# IntegratedSensor-nc8430win7.net
KiCad netlist of a schematic drawn in EAGLE
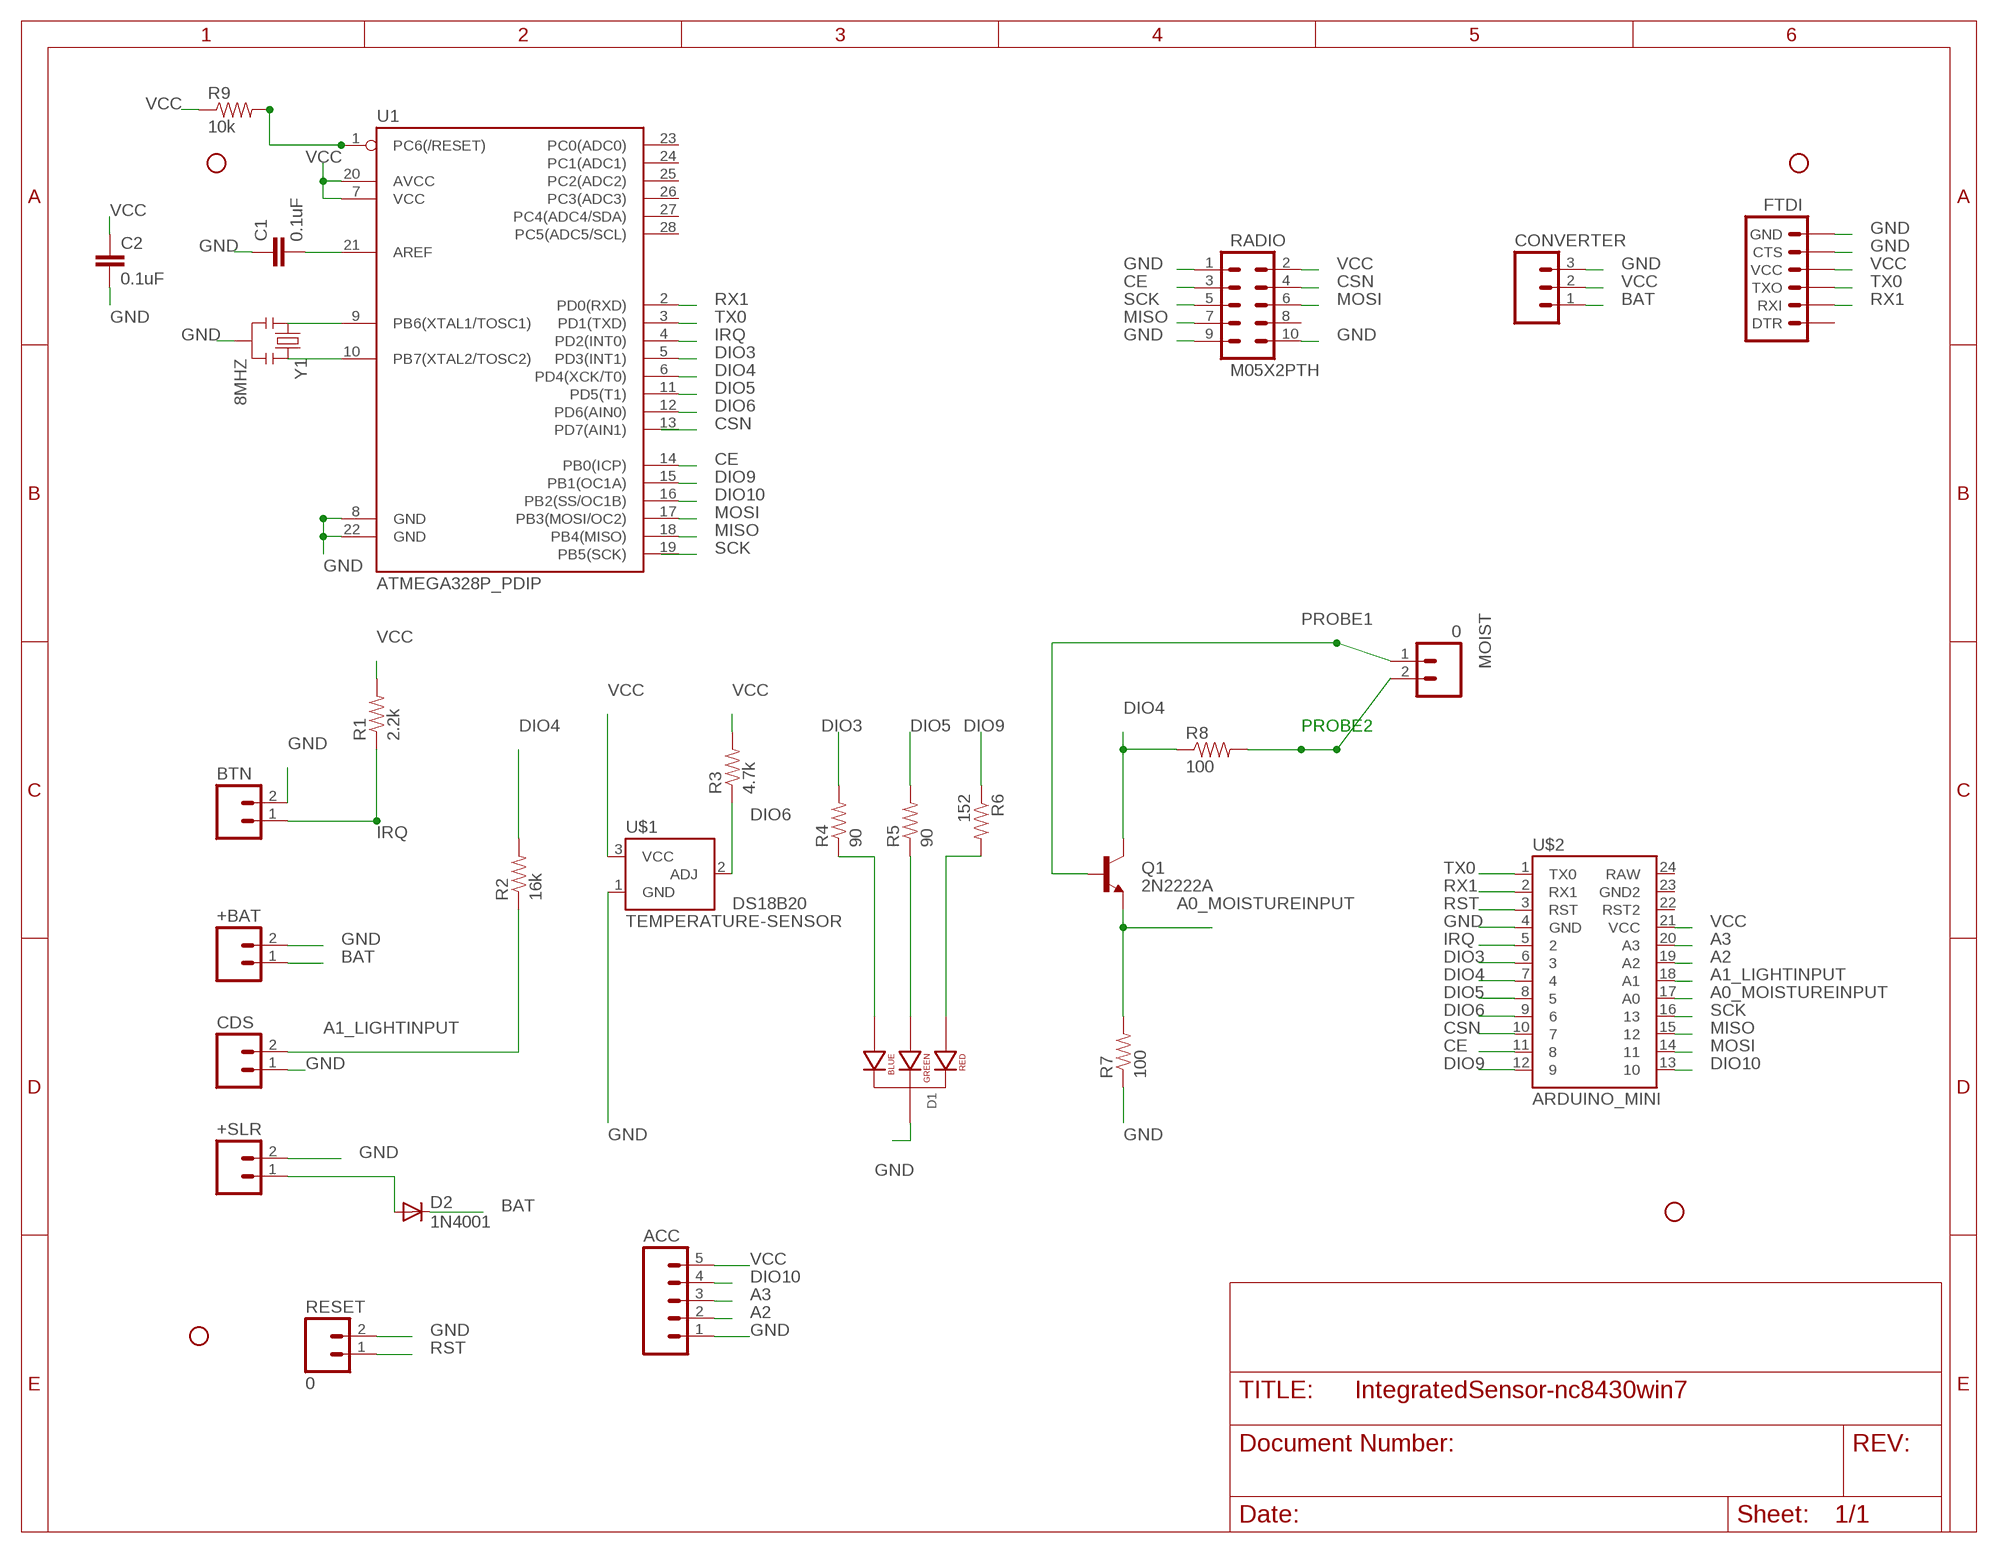
[diagram p0: schematic, sheet 1]

(export (version "E")
  (design (tool "Eeschema 10.0.6"))
  (components
    (comp (ref "+BAT")
      (value "M02PTH")
      (footprint "eagle-import:1X02")
      (libsource (lib "eagle-import") (part "M02PTH"))
    )
    (comp (ref "+SLR")
      (value "M02PTH")
      (footprint "eagle-import:1X02")
      (libsource (lib "eagle-import") (part "M02PTH"))
    )
    (comp (ref "ACC")
      (value "M05PTH")
      (footprint "eagle-import:1X05")
      (libsource (lib "eagle-import") (part "M05PTH"))
    )
    (comp (ref "BTN")
      (value "M02PTH")
      (footprint "eagle-import:1X02")
      (libsource (lib "eagle-import") (part "M02PTH"))
    )
    (comp (ref "C1")
      (value "0.1uF")
      (footprint "eagle-import:0402-CAP")
      (libsource (lib "eagle-import") (part "0.1UF-25V(+80/-20%)(0603)"))
    )
    (comp (ref "C2")
      (value "0.1uF")
      (footprint "eagle-import:0402-CAP")
      (libsource (lib "eagle-import") (part "0.1UF-25V(+80/-20%)(0603)"))
    )
    (comp (ref "CDS")
      (value "M02PTH")
      (footprint "eagle-import:1X02")
      (libsource (lib "eagle-import") (part "M02PTH"))
    )
    (comp (ref "CONVERTER")
      (value "M03PTH")
      (footprint "eagle-import:1X03")
      (libsource (lib "eagle-import") (part "M03PTH"))
    )
    (comp (ref "D1")
      (value "LED-RGB-CC-THRUCLEAR")
      (footprint "eagle-import:LED-RGB-THRU")
      (libsource (lib "eagle-import") (part "LED-RGB-CC-THRUCLEAR"))
    )
    (comp (ref "D2")
      (value "1N4001")
      (footprint "eagle-import:DIODE-1N4001")
      (libsource (lib "eagle-import") (part "DIODEPTH"))
    )
    (comp (ref "FTDI")
      (value "ARDUINO_SERIAL_PROGRAMPTH")
      (footprint "eagle-import:1X06")
      (libsource (lib "eagle-import") (part "ARDUINO_SERIAL_PROGRAMPTH"))
    )
    (comp (ref "MOIST")
      (value "0")
      (footprint "eagle-import:1X02")
      (libsource (lib "eagle-import") (part "M02PTH"))
    )
    (comp (ref "Q1")
      (value "2N2222A")
      (footprint "eagle-import:TO-92-AMMO")
      (libsource (lib "eagle-import") (part "TRANSISTOR_NPNTO-92-AMMO"))
    )
    (comp (ref "R1")
      (value "2.2k")
      (footprint "eagle-import:1_6W-RES")
      (libsource (lib "eagle-import") (part "RESISTORPTH-1/6W"))
    )
    (comp (ref "R2")
      (value "16k")
      (footprint "eagle-import:1_6W-RES")
      (libsource (lib "eagle-import") (part "RESISTORPTH-1/6W"))
    )
    (comp (ref "R3")
      (value "4.7k")
      (footprint "eagle-import:1_6W-RES")
      (libsource (lib "eagle-import") (part "RESISTORPTH-1/6W"))
    )
    (comp (ref "R4")
      (value "90")
      (footprint "eagle-import:1_6W-RES")
      (libsource (lib "eagle-import") (part "RESISTORPTH-1/6W"))
    )
    (comp (ref "R5")
      (value "90")
      (footprint "eagle-import:1_6W-RES")
      (libsource (lib "eagle-import") (part "RESISTORPTH-1/6W"))
    )
    (comp (ref "R6")
      (value "152")
      (footprint "eagle-import:1_6W-RES")
      (libsource (lib "eagle-import") (part "RESISTORPTH-1/6W"))
    )
    (comp (ref "R7")
      (value "100")
      (footprint "eagle-import:1_6W-RES")
      (libsource (lib "eagle-import") (part "RESISTORPTH-1/6W"))
    )
    (comp (ref "R8")
      (value "100")
      (footprint "eagle-import:1_6W-RES")
      (libsource (lib "eagle-import") (part "RESISTORPTH-1/6W"))
    )
    (comp (ref "R9")
      (value "10k")
      (footprint "eagle-import:1_6W-RES")
      (libsource (lib "eagle-import") (part "RESISTORPTH-1/6W"))
    )
    (comp (ref "RADIO")
      (value "M05X2PTH")
      (footprint "eagle-import:AVR_ICSP")
      (libsource (lib "eagle-import") (part "M05X2PTH"))
    )
    (comp (ref "RESET")
      (value "0")
      (footprint "eagle-import:1X02")
      (libsource (lib "eagle-import") (part "M02PTH"))
    )
    (comp (ref "STANDOFF1")
      (value "STAND-OFF")
      (footprint "eagle-import:STAND-OFF")
      (libsource (lib "eagle-import") (part "STAND-OFF"))
    )
    (comp (ref "STANDOFF2")
      (value "STAND-OFF")
      (footprint "eagle-import:STAND-OFF")
      (libsource (lib "eagle-import") (part "STAND-OFF"))
    )
    (comp (ref "STANDOFF3")
      (value "STAND-OFF")
      (footprint "eagle-import:STAND-OFF")
      (libsource (lib "eagle-import") (part "STAND-OFF"))
    )
    (comp (ref "STANDOFF4")
      (value "STAND-OFF")
      (footprint "eagle-import:STAND-OFF")
      (libsource (lib "eagle-import") (part "STAND-OFF"))
    )
    (comp (ref "U$1")
      (value "TEMPERATURE-SENSOR")
      (footprint "eagle-import:TO-92")
      (fields (field (name "PARTNAME") "DS18B20"))
      (libsource (lib "eagle-import") (part "TEMPERATURE-SENSOR"))
    )
    (comp (ref "U$2")
      (value "ARDUINO_MINI")
      (footprint "eagle-import:ARDUINO_MINI")
      (libsource (lib "eagle-import") (part "ARDUINO_MINI"))
    )
    (comp (ref "U1")
      (value "ATMEGA328P_PDIP")
      (footprint "eagle-import:DIL28-3")
      (libsource (lib "eagle-import") (part "ATMEGA328P_PDIP"))
    )
    (comp (ref "Y1")
      (value "8MHZ")
      (footprint "eagle-import:RESONATOR-SMD")
      (libsource (lib "eagle-import") (part "RESONATOR8MHZ"))
    )
  )
  (nets
    (net (code "1") (name "/A0_MOISTUREINPUT") (class "Default")
      (node (ref "Q1") (pin "1") (pinfunction "E_1") (pintype "passive"))
      (node (ref "R7") (pin "2") (pinfunction "2_2") (pintype "passive"))
      (node (ref "U$2") (pin "17") (pinfunction "A0_17") (pintype "bidirectional"))
    )
    (net (code "2") (name "/A1_LIGHTINPUT") (class "Default")
      (node (ref "CDS") (pin "2") (pinfunction "2_2") (pintype "passive"))
      (node (ref "R2") (pin "1") (pinfunction "1_1") (pintype "passive"))
      (node (ref "U$2") (pin "18") (pinfunction "A1_18") (pintype "bidirectional"))
    )
    (net (code "3") (name "/A2") (class "Default")
      (node (ref "ACC") (pin "2") (pinfunction "2_2") (pintype "passive"))
      (node (ref "U$2") (pin "19") (pinfunction "A2_19") (pintype "bidirectional"))
    )
    (net (code "4") (name "/A3") (class "Default")
      (node (ref "ACC") (pin "3") (pinfunction "3_3") (pintype "passive"))
      (node (ref "U$2") (pin "20") (pinfunction "A3_20") (pintype "bidirectional"))
    )
    (net (code "5") (name "/BAT") (class "Default")
      (node (ref "+BAT") (pin "1") (pinfunction "1_1") (pintype "passive"))
      (node (ref "CONVERTER") (pin "1") (pinfunction "1_1") (pintype "passive"))
      (node (ref "D2") (pin "C") (pinfunction "C_C") (pintype "passive"))
    )
    (net (code "6") (name "/CE") (class "Default")
      (node (ref "RADIO") (pin "3") (pinfunction "3_3") (pintype "passive"))
      (node (ref "U$2") (pin "11") (pinfunction "8_11") (pintype "bidirectional"))
      (node (ref "U1") (pin "14") (pinfunction "PB0(ICP)_14") (pintype "bidirectional"))
    )
    (net (code "7") (name "/CSN") (class "Default")
      (node (ref "RADIO") (pin "4") (pinfunction "4_4") (pintype "passive"))
      (node (ref "U$2") (pin "10") (pinfunction "7_10") (pintype "bidirectional"))
    )
    (net (code "8") (name "/DIO3") (class "Default")
      (node (ref "R4") (pin "2") (pinfunction "2_2") (pintype "passive"))
      (node (ref "U$2") (pin "6") (pinfunction "3_6") (pintype "bidirectional"))
      (node (ref "U1") (pin "5") (pinfunction "PD3(INT1)_5") (pintype "bidirectional"))
    )
    (net (code "9") (name "/DIO4") (class "Default")
      (node (ref "Q1") (pin "3") (pinfunction "C_3") (pintype "passive"))
      (node (ref "R2") (pin "2") (pinfunction "2_2") (pintype "passive"))
      (node (ref "R8") (pin "1") (pinfunction "1_1") (pintype "passive"))
      (node (ref "U$2") (pin "7") (pinfunction "4_7") (pintype "bidirectional"))
      (node (ref "U1") (pin "6") (pinfunction "PD4(XCK/T0)_6") (pintype "bidirectional"))
    )
    (net (code "10") (name "/DIO5") (class "Default")
      (node (ref "R5") (pin "2") (pinfunction "2_2") (pintype "passive"))
      (node (ref "U$2") (pin "8") (pinfunction "5_8") (pintype "bidirectional"))
      (node (ref "U1") (pin "11") (pinfunction "PD5(T1)_11") (pintype "bidirectional"))
    )
    (net (code "11") (name "/DIO6") (class "Default")
      (node (ref "R3") (pin "1") (pinfunction "1_1") (pintype "passive"))
      (node (ref "U$1") (pin "2") (pinfunction "ADJ_2") (pintype "bidirectional"))
      (node (ref "U$2") (pin "9") (pinfunction "6_9") (pintype "bidirectional"))
      (node (ref "U1") (pin "12") (pinfunction "PD6(AIN0)_12") (pintype "bidirectional"))
    )
    (net (code "12") (name "/DIO9") (class "Default")
      (node (ref "R6") (pin "1") (pinfunction "1_1") (pintype "passive"))
      (node (ref "U$2") (pin "12") (pinfunction "9_12") (pintype "bidirectional"))
      (node (ref "U1") (pin "15") (pinfunction "PB1(OC1A)_15") (pintype "bidirectional"))
    )
    (net (code "13") (name "/DIO10") (class "Default")
      (node (ref "ACC") (pin "4") (pinfunction "4_4") (pintype "passive"))
      (node (ref "U$2") (pin "13") (pinfunction "10_13") (pintype "bidirectional"))
      (node (ref "U1") (pin "16") (pinfunction "PB2(SS/OC1B)_16") (pintype "bidirectional"))
    )
    (net (code "14") (name "/GND") (class "Default")
      (node (ref "+BAT") (pin "2") (pinfunction "2_2") (pintype "passive"))
      (node (ref "+SLR") (pin "2") (pinfunction "2_2") (pintype "passive"))
      (node (ref "ACC") (pin "1") (pinfunction "1_1") (pintype "passive"))
      (node (ref "BTN") (pin "2") (pinfunction "2_2") (pintype "passive"))
      (node (ref "C1") (pin "1") (pinfunction "1_1") (pintype "passive"))
      (node (ref "C2") (pin "2") (pinfunction "2_2") (pintype "passive"))
      (node (ref "CDS") (pin "1") (pinfunction "1_1") (pintype "passive"))
      (node (ref "CONVERTER") (pin "3") (pinfunction "3_3") (pintype "passive"))
      (node (ref "D1") (pin "2") (pinfunction "CATHODE_2") (pintype "bidirectional"))
      (node (ref "FTDI") (pin "5") (pinfunction "CTS_5") (pintype "passive"))
      (node (ref "FTDI") (pin "6") (pinfunction "GND_6") (pintype "passive"))
      (node (ref "R7") (pin "1") (pinfunction "1_1") (pintype "passive"))
      (node (ref "RADIO") (pin "1") (pinfunction "1_1") (pintype "passive"))
      (node (ref "RADIO") (pin "10") (pinfunction "10_10") (pintype "passive"))
      (node (ref "RADIO") (pin "9") (pinfunction "9_9") (pintype "passive"))
      (node (ref "RESET") (pin "2") (pinfunction "2_2") (pintype "passive"))
      (node (ref "U$1") (pin "1") (pinfunction "GND_1") (pintype "bidirectional"))
      (node (ref "U$2") (pin "4") (pinfunction "GND_4") (pintype "bidirectional"))
      (node (ref "U1") (pin "22") (pinfunction "GND_22") (pintype "bidirectional"))
      (node (ref "U1") (pin "8") (pinfunction "GND_8") (pintype "bidirectional"))
      (node (ref "Y1") (pin "2") (pinfunction "2_2") (pintype "passive"))
    )
    (net (code "15") (name "/IRQ") (class "Default")
      (node (ref "BTN") (pin "1") (pinfunction "1_1") (pintype "passive"))
      (node (ref "R1") (pin "1") (pinfunction "1_1") (pintype "passive"))
      (node (ref "U$2") (pin "5") (pinfunction "2_5") (pintype "bidirectional"))
      (node (ref "U1") (pin "4") (pinfunction "PD2(INT0)_4") (pintype "bidirectional"))
    )
    (net (code "16") (name "/MISO") (class "Default")
      (node (ref "RADIO") (pin "7") (pinfunction "7_7") (pintype "passive"))
      (node (ref "U$2") (pin "15") (pinfunction "12_15") (pintype "bidirectional"))
      (node (ref "U1") (pin "18") (pinfunction "PB4(MISO)_18") (pintype "bidirectional"))
    )
    (net (code "17") (name "/MOSI") (class "Default")
      (node (ref "RADIO") (pin "6") (pinfunction "6_6") (pintype "passive"))
      (node (ref "U$2") (pin "14") (pinfunction "11_14") (pintype "bidirectional"))
      (node (ref "U1") (pin "17") (pinfunction "PB3(MOSI/OC2)_17") (pintype "bidirectional"))
    )
    (net (code "18") (name "/PROBE1") (class "Default")
      (node (ref "MOIST") (pin "1") (pinfunction "1_1") (pintype "passive"))
      (node (ref "Q1") (pin "2") (pinfunction "B_2") (pintype "passive"))
    )
    (net (code "19") (name "/PROBE2") (class "Default")
      (node (ref "MOIST") (pin "2") (pinfunction "2_2") (pintype "passive"))
      (node (ref "R8") (pin "2") (pinfunction "2_2") (pintype "passive"))
    )
    (net (code "20") (name "/RST") (class "Default")
      (node (ref "RESET") (pin "1") (pinfunction "1_1") (pintype "passive"))
      (node (ref "U$2") (pin "3") (pinfunction "RST_3") (pintype "bidirectional"))
    )
    (net (code "21") (name "/RX1") (class "Default")
      (node (ref "FTDI") (pin "2") (pinfunction "RXI_2") (pintype "passive"))
      (node (ref "U$2") (pin "2") (pinfunction "RX1_2") (pintype "bidirectional"))
      (node (ref "U1") (pin "2") (pinfunction "PD0(RXD)_2") (pintype "bidirectional"))
    )
    (net (code "22") (name "/SCK") (class "Default")
      (node (ref "RADIO") (pin "5") (pinfunction "5_5") (pintype "passive"))
      (node (ref "U$2") (pin "16") (pinfunction "13_16") (pintype "bidirectional"))
    )
    (net (code "23") (name "/TX0") (class "Default")
      (node (ref "FTDI") (pin "3") (pinfunction "TXO_3") (pintype "passive"))
      (node (ref "U$2") (pin "1") (pinfunction "TX0_1") (pintype "bidirectional"))
      (node (ref "U1") (pin "3") (pinfunction "PD1(TXD)_3") (pintype "bidirectional"))
    )
    (net (code "24") (name "/VCC") (class "Default")
      (node (ref "ACC") (pin "5") (pinfunction "5_5") (pintype "passive"))
      (node (ref "C2") (pin "1") (pinfunction "1_1") (pintype "passive"))
      (node (ref "CONVERTER") (pin "2") (pinfunction "2_2") (pintype "passive"))
      (node (ref "FTDI") (pin "4") (pinfunction "VCC_4") (pintype "passive"))
      (node (ref "R1") (pin "2") (pinfunction "2_2") (pintype "passive"))
      (node (ref "R3") (pin "2") (pinfunction "2_2") (pintype "passive"))
      (node (ref "R9") (pin "1") (pinfunction "1_1") (pintype "passive"))
      (node (ref "RADIO") (pin "2") (pinfunction "2_2") (pintype "passive"))
      (node (ref "U$1") (pin "3") (pinfunction "VCC_3") (pintype "bidirectional"))
      (node (ref "U$2") (pin "21") (pinfunction "VCC_21") (pintype "bidirectional"))
      (node (ref "U1") (pin "20") (pinfunction "AVCC_20") (pintype "bidirectional"))
      (node (ref "U1") (pin "7") (pinfunction "VCC_7") (pintype "bidirectional"))
    )
    (net (code "25") (name "Net-(+SLR-Pad1)") (class "Default")
      (node (ref "+SLR") (pin "1") (pinfunction "1_1") (pintype "passive"))
      (node (ref "D2") (pin "A") (pinfunction "A_A") (pintype "passive"))
    )
    (net (code "26") (name "Net-(D1-BLUE_CATHODE)") (class "Default")
      (node (ref "D1") (pin "4") (pinfunction "BLUE_CATHODE_4") (pintype "bidirectional"))
      (node (ref "R4") (pin "1") (pinfunction "1_1") (pintype "passive"))
    )
    (net (code "27") (name "Net-(D1-GREEN_CATHODE)") (class "Default")
      (node (ref "D1") (pin "3") (pinfunction "GREEN_CATHODE_3") (pintype "bidirectional"))
      (node (ref "R5") (pin "1") (pinfunction "1_1") (pintype "passive"))
    )
    (net (code "28") (name "Net-(D1-RED_CATHODE)") (class "Default")
      (node (ref "D1") (pin "1") (pinfunction "RED_CATHODE_1") (pintype "bidirectional"))
      (node (ref "R6") (pin "2") (pinfunction "2_2") (pintype "passive"))
    )
    (net (code "29") (name "Net-(U1-AREF)") (class "Default")
      (node (ref "C1") (pin "2") (pinfunction "2_2") (pintype "passive"))
      (node (ref "U1") (pin "21") (pinfunction "AREF_21") (pintype "bidirectional"))
    )
    (net (code "30") (name "Net-(U1-PB6(XTAL1{slash}TOSC1))") (class "Default")
      (node (ref "U1") (pin "9") (pinfunction "PB6(XTAL1/TOSC1)_9") (pintype "bidirectional"))
      (node (ref "Y1") (pin "1") (pinfunction "1_1") (pintype "passive"))
    )
    (net (code "31") (name "Net-(U1-PB7(XTAL2{slash}TOSC2))") (class "Default")
      (node (ref "U1") (pin "10") (pinfunction "PB7(XTAL2/TOSC2)_10") (pintype "bidirectional"))
      (node (ref "Y1") (pin "3") (pinfunction "3_3") (pintype "passive"))
    )
    (net (code "32") (name "Net-(U1-PC6({slash}RESET))") (class "Default")
      (node (ref "R9") (pin "2") (pinfunction "2_2") (pintype "passive"))
      (node (ref "U1") (pin "1") (pinfunction "PC6(/RESET)_1") (pintype "bidirectional"))
    )
    (net (code "33") (name "unconnected-(FTDI-DTR-Pad1)") (class "Default")
      (node (ref "FTDI") (pin "1") (pinfunction "DTR_1") (pintype "passive"))
    )
    (net (code "34") (name "unconnected-(RADIO-Pad8)") (class "Default")
      (node (ref "RADIO") (pin "8") (pinfunction "8_8") (pintype "passive"))
    )
    (net (code "35") (name "unconnected-(U$2-GND2-Pad23)") (class "Default")
      (node (ref "U$2") (pin "23") (pinfunction "GND2_23") (pintype "bidirectional"))
    )
    (net (code "36") (name "unconnected-(U$2-RAW-Pad24)") (class "Default")
      (node (ref "U$2") (pin "24") (pinfunction "RAW_24") (pintype "bidirectional"))
    )
    (net (code "37") (name "unconnected-(U$2-RST2-Pad22)") (class "Default")
      (node (ref "U$2") (pin "22") (pinfunction "RST2_22") (pintype "bidirectional"))
    )
    (net (code "38") (name "unconnected-(U1-PB5(SCK)-Pad19)") (class "Default")
      (node (ref "U1") (pin "19") (pinfunction "PB5(SCK)_19") (pintype "bidirectional"))
    )
    (net (code "39") (name "unconnected-(U1-PC0(ADC0)-Pad23)") (class "Default")
      (node (ref "U1") (pin "23") (pinfunction "PC0(ADC0)_23") (pintype "bidirectional"))
    )
    (net (code "40") (name "unconnected-(U1-PC1(ADC1)-Pad24)") (class "Default")
      (node (ref "U1") (pin "24") (pinfunction "PC1(ADC1)_24") (pintype "bidirectional"))
    )
    (net (code "41") (name "unconnected-(U1-PC2(ADC2)-Pad25)") (class "Default")
      (node (ref "U1") (pin "25") (pinfunction "PC2(ADC2)_25") (pintype "bidirectional"))
    )
    (net (code "42") (name "unconnected-(U1-PC3(ADC3)-Pad26)") (class "Default")
      (node (ref "U1") (pin "26") (pinfunction "PC3(ADC3)_26") (pintype "bidirectional"))
    )
    (net (code "43") (name "unconnected-(U1-PC4(ADC4{slash}SDA)-Pad27)") (class "Default")
      (node (ref "U1") (pin "27") (pinfunction "PC4(ADC4/SDA)_27") (pintype "bidirectional"))
    )
    (net (code "44") (name "unconnected-(U1-PC5(ADC5{slash}SCL)-Pad28)") (class "Default")
      (node (ref "U1") (pin "28") (pinfunction "PC5(ADC5/SCL)_28") (pintype "bidirectional"))
    )
    (net (code "45") (name "unconnected-(U1-PD7(AIN1)-Pad13)") (class "Default")
      (node (ref "U1") (pin "13") (pinfunction "PD7(AIN1)_13") (pintype "bidirectional"))
    )
  )
)
